# electron_v011.net
KiCad netlist of a schematic drawn in EAGLE
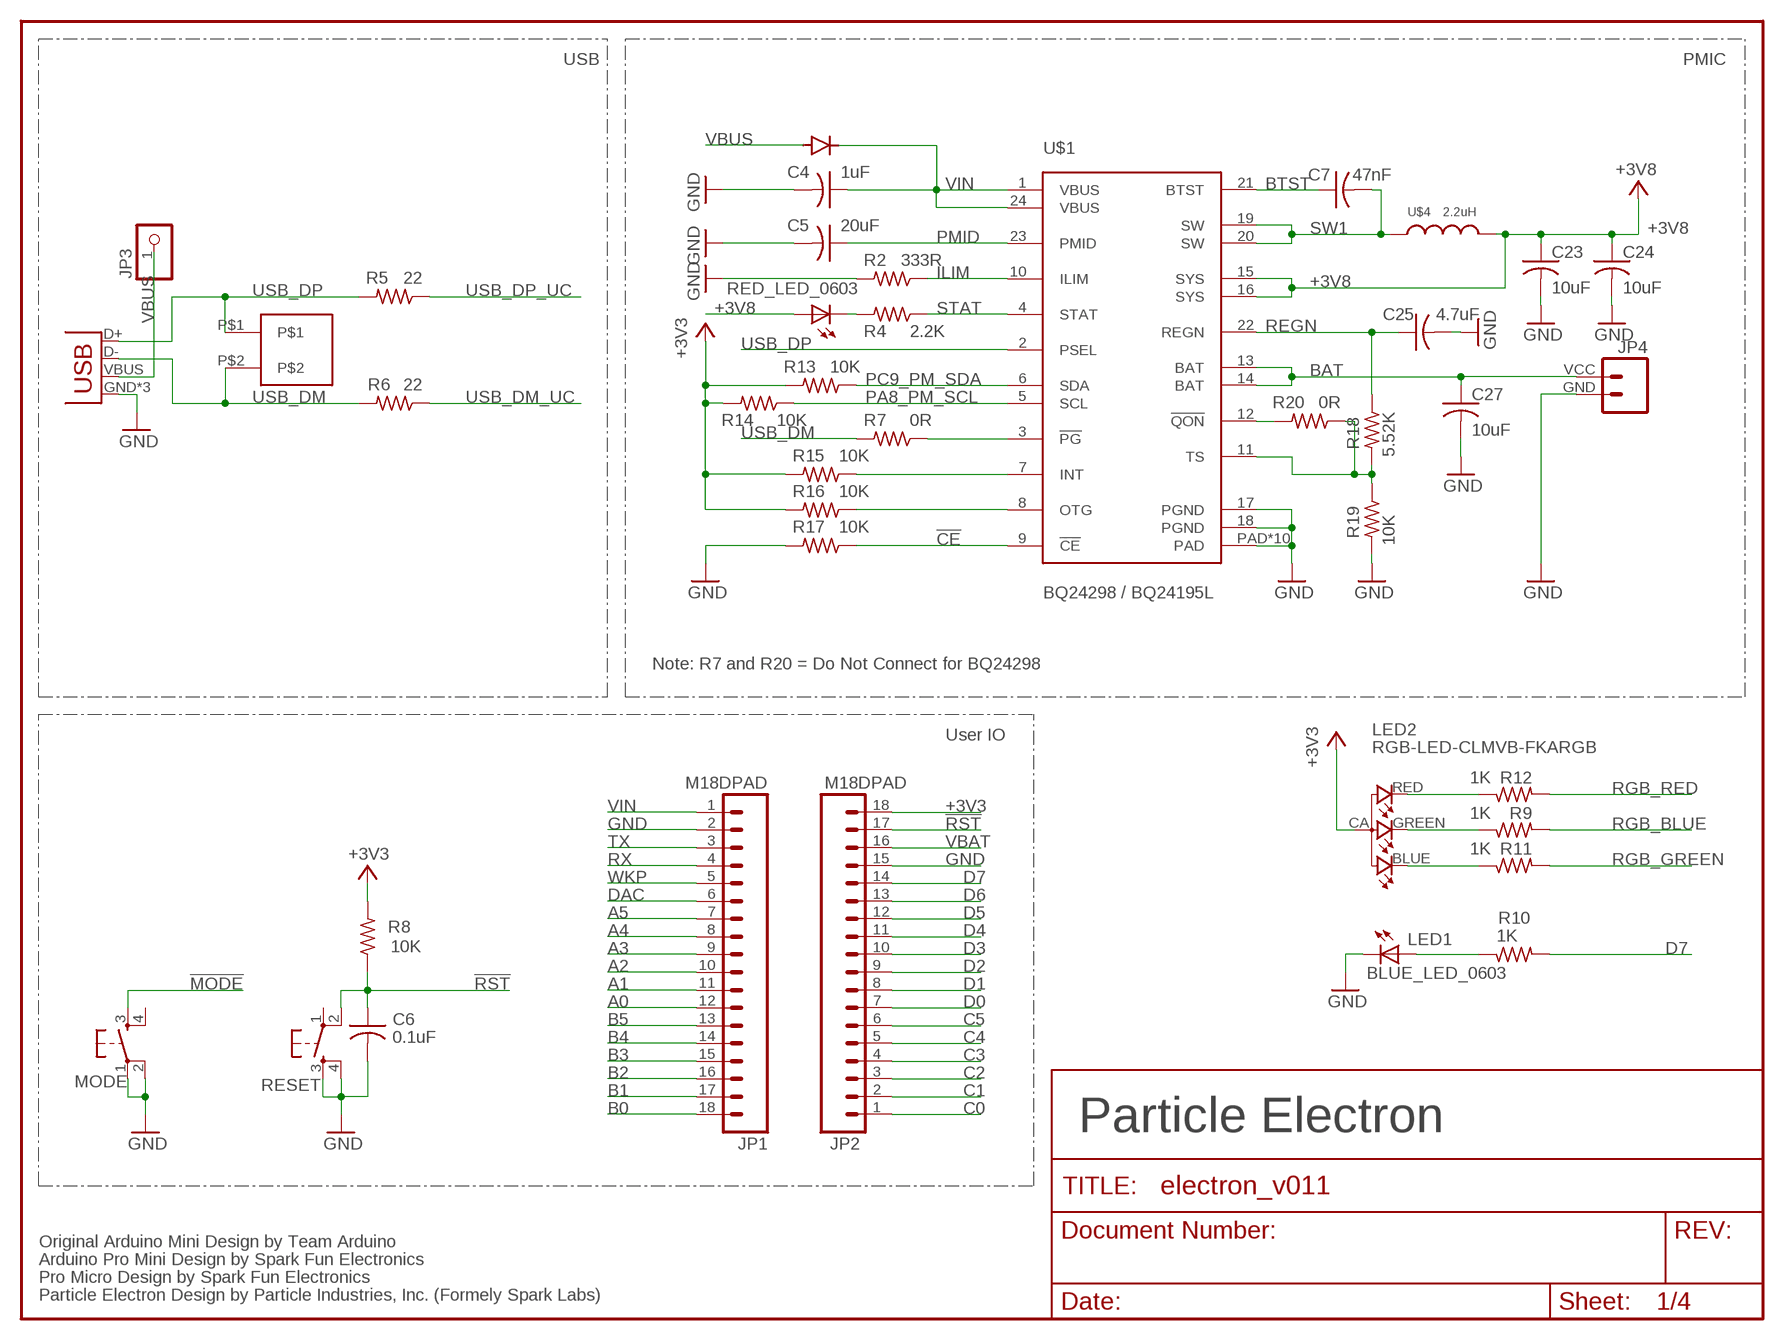
[diagram p0: schematic, sheet 1]
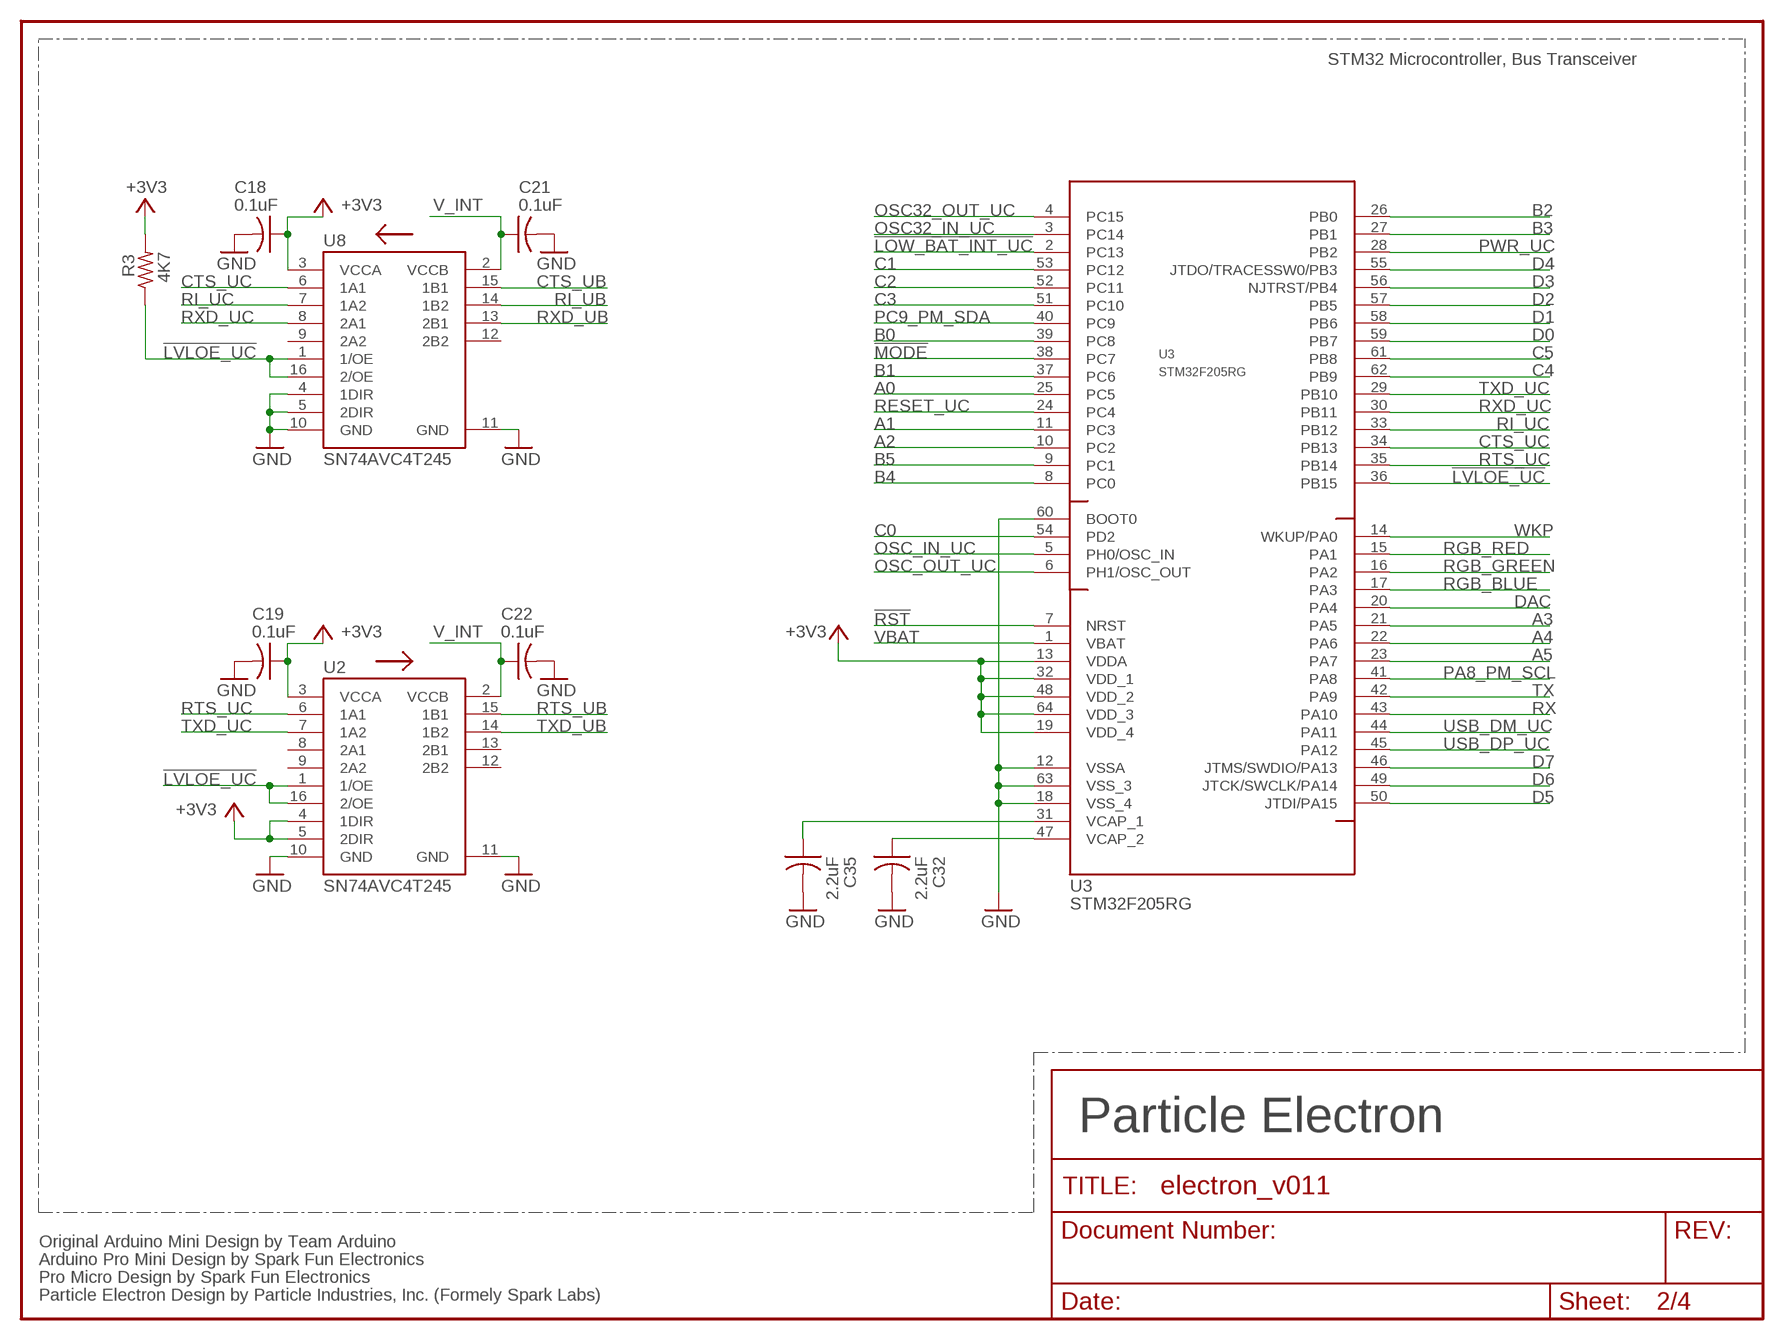
[diagram p1: schematic, sheet 2]
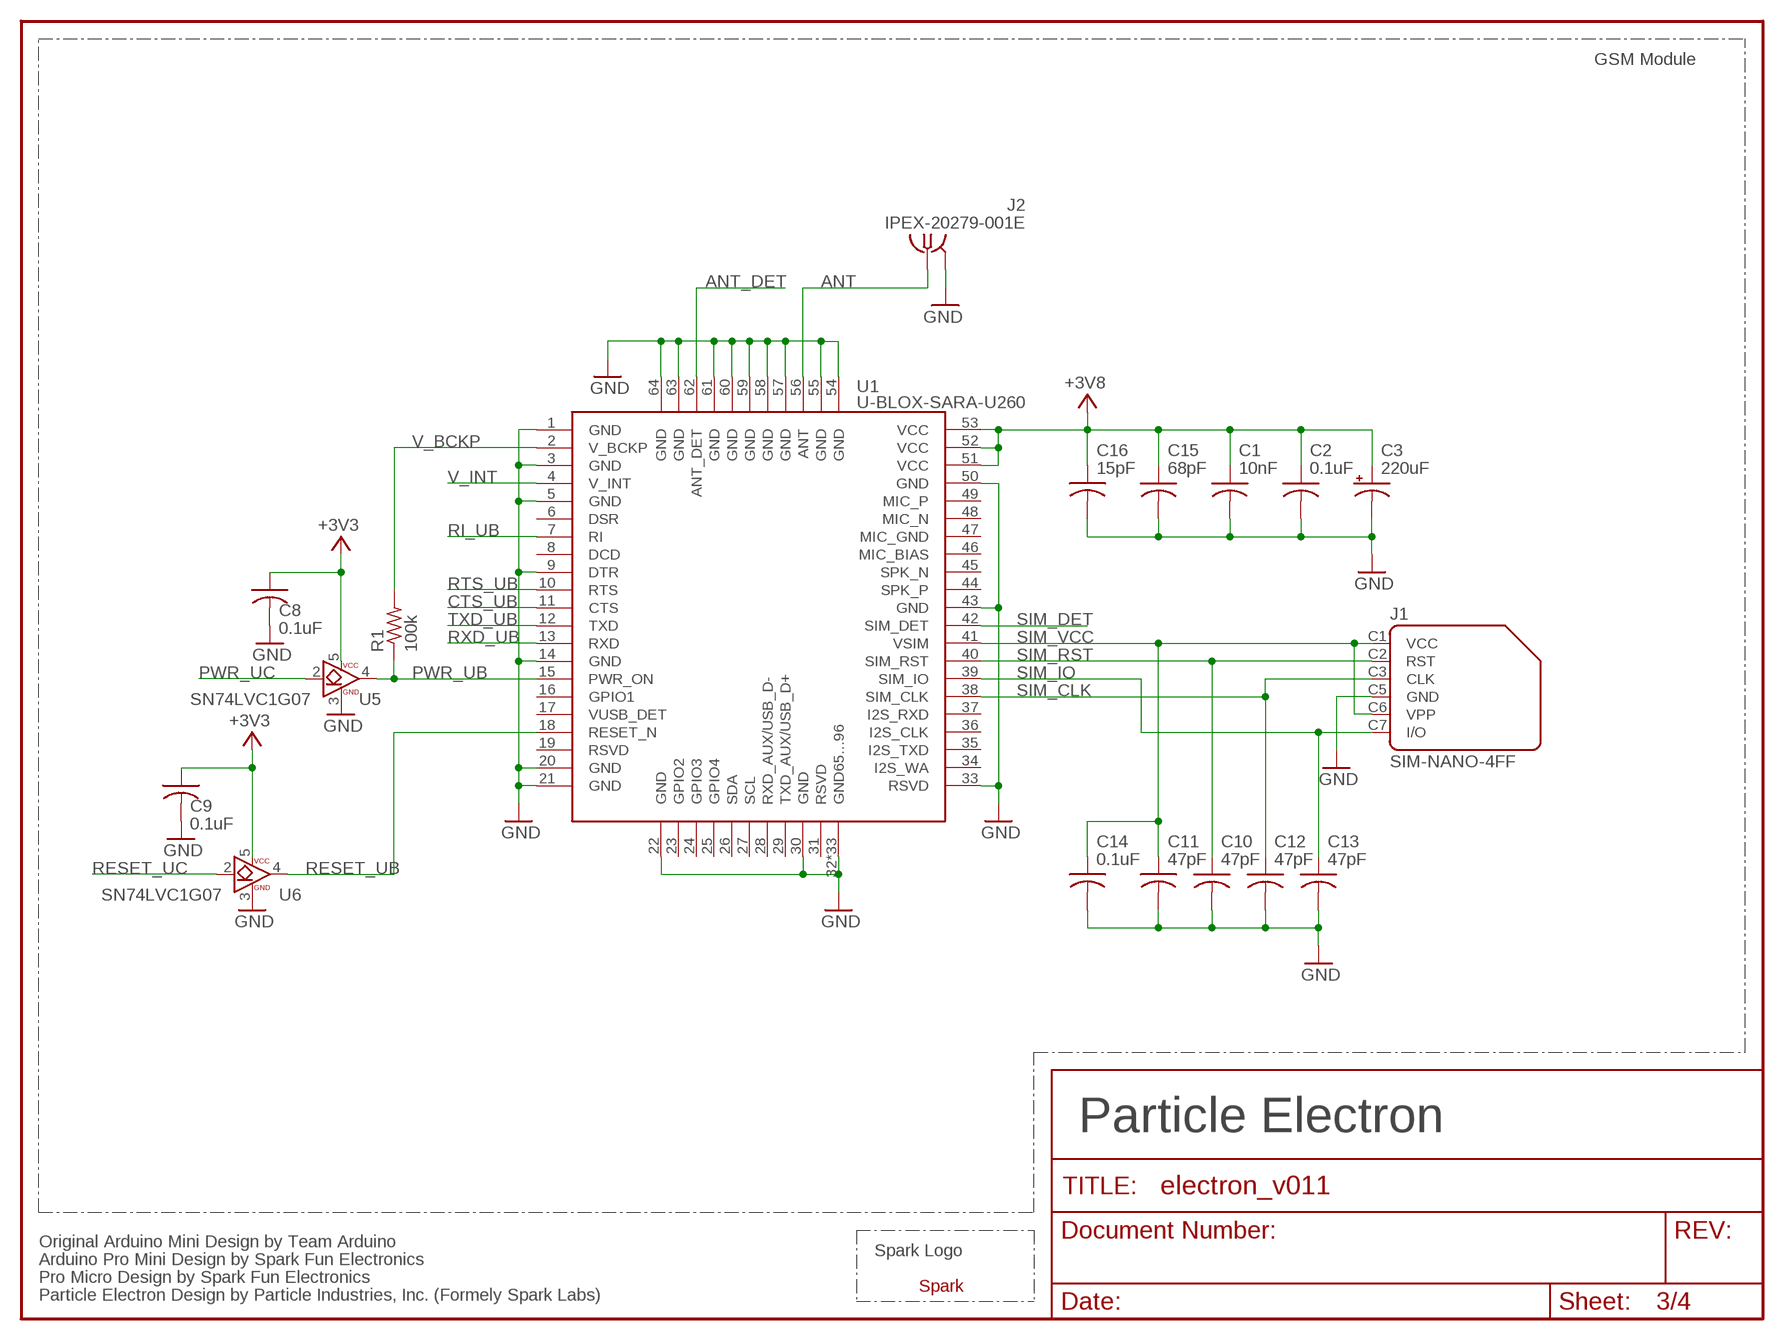
[diagram p2: schematic, sheet 3]
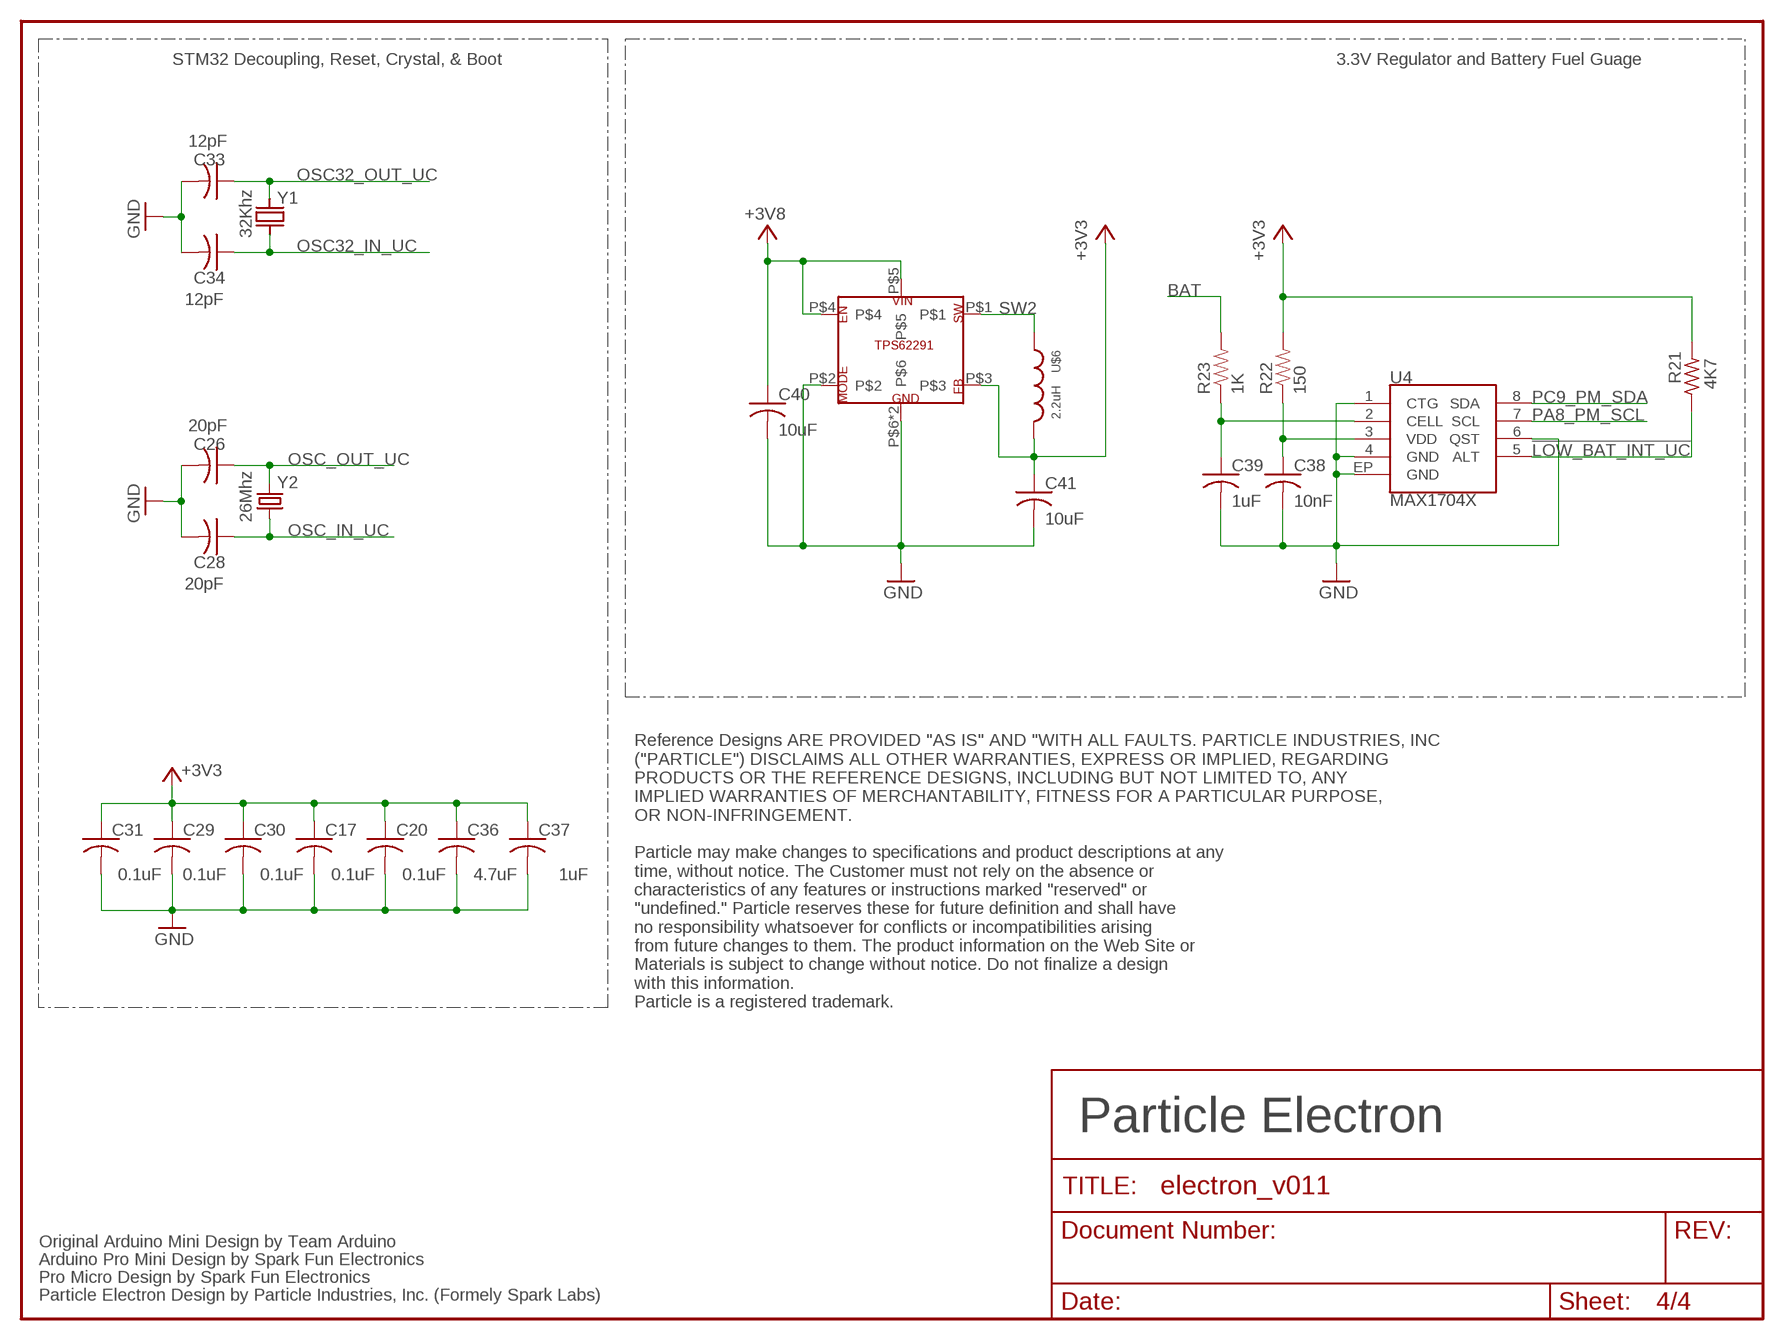
[diagram p3: schematic, sheet 4]

(export (version "E")
  (design (tool "Eeschema 10.0.6"))
  (components
    (comp (ref "C1")
      (value "10nF")
      (footprint "eagle-import:C0402_B")
      (libsource (lib "eagle-import") (part "C-US"))
    )
    (comp (ref "C2")
      (value "0.1uF")
      (footprint "eagle-import:C0402_B")
      (libsource (lib "eagle-import") (part "C-US"))
    )
    (comp (ref "C3")
      (value "220uF")
      (footprint "eagle-import:C_6032-28R")
      (libsource (lib "eagle-import") (part "CPOL-USC/6032-28R"))
    )
    (comp (ref "C8")
      (value "0.1uF")
      (footprint "eagle-import:C0402_B")
      (libsource (lib "eagle-import") (part "C-US"))
    )
    (comp (ref "C9")
      (value "0.1uF")
      (footprint "eagle-import:C0402_B")
      (libsource (lib "eagle-import") (part "C-US"))
    )
    (comp (ref "C10")
      (value "47pF")
      (footprint "eagle-import:C0402_B")
      (libsource (lib "eagle-import") (part "C-US"))
    )
    (comp (ref "C11")
      (value "47pF")
      (footprint "eagle-import:C0402_B")
      (libsource (lib "eagle-import") (part "C-US"))
    )
    (comp (ref "C12")
      (value "47pF")
      (footprint "eagle-import:C0402_B")
      (libsource (lib "eagle-import") (part "C-US"))
    )
    (comp (ref "C13")
      (value "47pF")
      (footprint "eagle-import:C0402_B")
      (libsource (lib "eagle-import") (part "C-US"))
    )
    (comp (ref "C14")
      (value "0.1uF")
      (footprint "eagle-import:C0402_B")
      (libsource (lib "eagle-import") (part "C-US"))
    )
    (comp (ref "C15")
      (value "68pF")
      (footprint "eagle-import:C0402_B")
      (libsource (lib "eagle-import") (part "C-US"))
    )
    (comp (ref "C16")
      (value "15pF")
      (footprint "eagle-import:C0402_B")
      (libsource (lib "eagle-import") (part "C-US"))
    )
    (comp (ref "J1")
      (value "SIM-NANO-4FF")
      (footprint "eagle-import:GCT-SIM8100")
      (libsource (lib "eagle-import") (part "SIM-NANO-4FF"))
    )
    (comp (ref "J2")
      (value "IPEX-20279-001E")
      (footprint "eagle-import:IPEX-20279-001E")
      (libsource (lib "eagle-import") (part "IPEX-20279-001E"))
    )
    (comp (ref "R1")
      (value "100k")
      (footprint "eagle-import:R0402_B")
      (libsource (lib "eagle-import") (part "R-US_"))
    )
    (comp (ref "U$2")
      (value "SPARK_LOGO2")
      (footprint "eagle-import:SPARK_LOGO2")
      (libsource (lib "eagle-import") (part "SPARK_LOGO2"))
    )
    (comp (ref "U1")
      (value "U-BLOX-SARA-U260")
      (footprint "eagle-import:U-BLOX-SARA-U2")
      (libsource (lib "eagle-import") (part "U-BLOX-SARA-U260"))
    )
    (comp (ref "U5")
      (value "SN74LVC1G07")
      (footprint "eagle-import:SC-70-5")
      (libsource (lib "eagle-import") (part "SN74LVC1G07"))
    )
    (comp (ref "U6")
      (value "SN74LVC1G07")
      (footprint "eagle-import:SC-70-5")
      (libsource (lib "eagle-import") (part "SN74LVC1G07"))
    )
    (comp (ref "BLUE_LED_0603")
      (value "LED0603")
      (footprint "eagle-import:LED-0603")
      (libsource (lib "eagle-import") (part "LED0603"))
    )
    (comp (ref "C4")
      (value "1uF")
      (footprint "eagle-import:C0603_B")
      (libsource (lib "eagle-import") (part "C-US0603"))
    )
    (comp (ref "C5")
      (value "20uF")
      (footprint "eagle-import:C0603_B")
      (libsource (lib "eagle-import") (part "C-US0603"))
    )
    (comp (ref "C6")
      (value "0.1uF")
      (footprint "eagle-import:C0402_B")
      (libsource (lib "eagle-import") (part "C-US"))
    )
    (comp (ref "C7")
      (value "47nF")
      (footprint "eagle-import:C0402_B")
      (libsource (lib "eagle-import") (part "C-US"))
    )
    (comp (ref "C23")
      (value "10uF")
      (footprint "eagle-import:C0603_B")
      (libsource (lib "eagle-import") (part "C-US0603"))
    )
    (comp (ref "C24")
      (value "10uF")
      (footprint "eagle-import:C0603_B")
      (libsource (lib "eagle-import") (part "C-US0603"))
    )
    (comp (ref "C25")
      (value "4.7uF")
      (footprint "eagle-import:C0603_B")
      (libsource (lib "eagle-import") (part "C-US0603"))
    )
    (comp (ref "C27")
      (value "10uF")
      (footprint "eagle-import:C0603_B")
      (libsource (lib "eagle-import") (part "C-US0603"))
    )
    (comp (ref "JP1")
      (value "M18DPAD")
      (footprint "eagle-import:1X18-D-PADS")
      (libsource (lib "eagle-import") (part "M18DPAD"))
    )
    (comp (ref "JP2")
      (value "M18DPAD")
      (footprint "eagle-import:1X18-D-PADS")
      (libsource (lib "eagle-import") (part "M18DPAD"))
    )
    (comp (ref "JP3")
      (value "PINHD-1X1")
      (footprint "eagle-import:1X01")
      (libsource (lib "eagle-import") (part "PINHD-1X1"))
    )
    (comp (ref "JP4")
      (value "M024UCON-15767")
      (footprint "eagle-import:JST-2-SMD-VERT")
      (libsource (lib "eagle-import") (part "M024UCON-15767"))
    )
    (comp (ref "LED2")
      (value "RGB-LED-CLMVB-FKARGB")
      (footprint "eagle-import:PLCC4-2MM-RGB")
      (libsource (lib "eagle-import") (part "RGB-LED-CLMVB-FKARGB"))
    )
    (comp (ref "MODE")
      (value "KMR211GLFS")
      (footprint "eagle-import:TACTILE_SWITCH_SMD")
      (libsource (lib "eagle-import") (part "TAC_SWITCHSMD"))
    )
    (comp (ref "R2")
      (value "333R")
      (footprint "eagle-import:R0402_B")
      (libsource (lib "eagle-import") (part "R-US_"))
    )
    (comp (ref "R4")
      (value "2.2K")
      (footprint "eagle-import:R0402_B")
      (libsource (lib "eagle-import") (part "R-US_"))
    )
    (comp (ref "R5")
      (value "22")
      (footprint "eagle-import:R0402_B")
      (libsource (lib "eagle-import") (part "R-US_"))
    )
    (comp (ref "R6")
      (value "22")
      (footprint "eagle-import:R0402_B")
      (libsource (lib "eagle-import") (part "R-US_"))
    )
    (comp (ref "R7")
      (value "0R")
      (footprint "eagle-import:R0402_B")
      (libsource (lib "eagle-import") (part "R-US_"))
    )
    (comp (ref "R8")
      (value "10K")
      (footprint "eagle-import:R0402_B")
      (libsource (lib "eagle-import") (part "R-US_"))
    )
    (comp (ref "R9")
      (value "1K")
      (footprint "eagle-import:R0402_B")
      (libsource (lib "eagle-import") (part "R-US_"))
    )
    (comp (ref "R10")
      (value "1K")
      (footprint "eagle-import:R0402_B")
      (libsource (lib "eagle-import") (part "R-US_"))
    )
    (comp (ref "R11")
      (value "1K")
      (footprint "eagle-import:R0402_B")
      (libsource (lib "eagle-import") (part "R-US_"))
    )
    (comp (ref "R12")
      (value "1K")
      (footprint "eagle-import:R0402_B")
      (libsource (lib "eagle-import") (part "R-US_"))
    )
    (comp (ref "R13")
      (value "10K")
      (footprint "eagle-import:R0402_B")
      (libsource (lib "eagle-import") (part "R-US_"))
    )
    (comp (ref "R14")
      (value "10K")
      (footprint "eagle-import:R0402_B")
      (libsource (lib "eagle-import") (part "R-US_"))
    )
    (comp (ref "R15")
      (value "10K")
      (footprint "eagle-import:R0402_B")
      (libsource (lib "eagle-import") (part "R-US_"))
    )
    (comp (ref "R16")
      (value "10K")
      (footprint "eagle-import:R0402_B")
      (libsource (lib "eagle-import") (part "R-US_"))
    )
    (comp (ref "R17")
      (value "10K")
      (footprint "eagle-import:R0402_B")
      (libsource (lib "eagle-import") (part "R-US_"))
    )
    (comp (ref "R18")
      (value "5.52K")
      (footprint "eagle-import:R0402_B")
      (libsource (lib "eagle-import") (part "R-US_"))
    )
    (comp (ref "R19")
      (value "10K")
      (footprint "eagle-import:R0402_B")
      (libsource (lib "eagle-import") (part "R-US_"))
    )
    (comp (ref "R20")
      (value "0R")
      (footprint "eagle-import:R0402_B")
      (libsource (lib "eagle-import") (part "R-US_"))
    )
    (comp (ref "RED_LED_0603")
      (value "LED0603")
      (footprint "eagle-import:LED-0603")
      (libsource (lib "eagle-import") (part "LED0603"))
    )
    (comp (ref "RESET")
      (value "KMR211GLFS")
      (footprint "eagle-import:TACTILE_SWITCH_SMD")
      (libsource (lib "eagle-import") (part "TAC_SWITCHSMD"))
    )
    (comp (ref "U$1")
      (value "BQ24298 / BQ24195L")
      (footprint "eagle-import:QFN24")
      (libsource (lib "eagle-import") (part "BQ24298RTWR"))
    )
    (comp (ref "U$3")
      (value "DIODE")
      (footprint "eagle-import:DIODE-DO-220AA(SMP)")
      (libsource (lib "eagle-import") (part "DIODE"))
    )
    (comp (ref "U$4")
      (value "2.2uH")
      (footprint "eagle-import:INDUCTOR-4020")
      (libsource (lib "eagle-import") (part "INDUCTORH"))
    )
    (comp (ref "U$7")
      (value "M02_0.05_HEADER")
      (footprint "eagle-import:M02_0.05_HEADER")
      (libsource (lib "eagle-import") (part "M02_0.05_HEADER"))
    )
    (comp (ref "X1")
      (value "USB-MICROB")
      (footprint "eagle-import:USB-MICROB-SLOT-HOLE")
      (libsource (lib "eagle-import") (part "USBUSB-MICROB-SLOT-HOLE"))
    )
    (comp (ref "C18")
      (value "0.1uF")
      (footprint "eagle-import:C0402_B")
      (libsource (lib "eagle-import") (part "C-US"))
    )
    (comp (ref "C19")
      (value "0.1uF")
      (footprint "eagle-import:C0402_B")
      (libsource (lib "eagle-import") (part "C-US"))
    )
    (comp (ref "C21")
      (value "0.1uF")
      (footprint "eagle-import:C0402_B")
      (libsource (lib "eagle-import") (part "C-US"))
    )
    (comp (ref "C22")
      (value "0.1uF")
      (footprint "eagle-import:C0402_B")
      (libsource (lib "eagle-import") (part "C-US"))
    )
    (comp (ref "C32")
      (value "2.2uF")
      (footprint "eagle-import:C0402_B")
      (libsource (lib "eagle-import") (part "C-US"))
    )
    (comp (ref "C35")
      (value "2.2uF")
      (footprint "eagle-import:C0402_B")
      (libsource (lib "eagle-import") (part "C-US"))
    )
    (comp (ref "R3")
      (value "4K7")
      (footprint "eagle-import:R0402_B")
      (libsource (lib "eagle-import") (part "R-US_"))
    )
    (comp (ref "U2")
      (value "SN74AVC4T245")
      (footprint "eagle-import:UFQFN-16")
      (libsource (lib "eagle-import") (part "SN74AVC4T245"))
    )
    (comp (ref "U3")
      (value "STM32F205RG")
      (footprint "eagle-import:LQFP64")
      (libsource (lib "eagle-import") (part "STM32F20XR"))
    )
    (comp (ref "U8")
      (value "SN74AVC4T245")
      (footprint "eagle-import:UFQFN-16")
      (libsource (lib "eagle-import") (part "SN74AVC4T245"))
    )
    (comp (ref "C17")
      (value "0.1uF")
      (footprint "eagle-import:C0402_B")
      (libsource (lib "eagle-import") (part "C-US"))
    )
    (comp (ref "C20")
      (value "0.1uF")
      (footprint "eagle-import:C0402_B")
      (libsource (lib "eagle-import") (part "C-US"))
    )
    (comp (ref "C26")
      (value "20pF")
      (footprint "eagle-import:C0402_B")
      (libsource (lib "eagle-import") (part "C-US"))
    )
    (comp (ref "C28")
      (value "20pF")
      (footprint "eagle-import:C0402_B")
      (libsource (lib "eagle-import") (part "C-US"))
    )
    (comp (ref "C29")
      (value "0.1uF")
      (footprint "eagle-import:C0402_B")
      (libsource (lib "eagle-import") (part "C-US"))
    )
    (comp (ref "C30")
      (value "0.1uF")
      (footprint "eagle-import:C0402_B")
      (libsource (lib "eagle-import") (part "C-US"))
    )
    (comp (ref "C31")
      (value "0.1uF")
      (footprint "eagle-import:C0402_B")
      (libsource (lib "eagle-import") (part "C-US"))
    )
    (comp (ref "C33")
      (value "12pF")
      (footprint "eagle-import:C0402_B")
      (libsource (lib "eagle-import") (part "C-US"))
    )
    (comp (ref "C34")
      (value "12pF")
      (footprint "eagle-import:C0402_B")
      (libsource (lib "eagle-import") (part "C-US"))
    )
    (comp (ref "C36")
      (value "4.7uF")
      (footprint "eagle-import:C0402_B")
      (libsource (lib "eagle-import") (part "C-US"))
    )
    (comp (ref "C37")
      (value "1uF")
      (footprint "eagle-import:C0402_B")
      (libsource (lib "eagle-import") (part "C-US"))
    )
    (comp (ref "C38")
      (value "10nF")
      (footprint "eagle-import:C0402_B")
      (libsource (lib "eagle-import") (part "C-US"))
    )
    (comp (ref "C39")
      (value "1uF")
      (footprint "eagle-import:C0402_B")
      (libsource (lib "eagle-import") (part "C-US"))
    )
    (comp (ref "C40")
      (value "10uF")
      (footprint "eagle-import:C0603_B")
      (libsource (lib "eagle-import") (part "C-US0603"))
    )
    (comp (ref "C41")
      (value "10uF")
      (footprint "eagle-import:C0603_B")
      (libsource (lib "eagle-import") (part "C-US0603"))
    )
    (comp (ref "R21")
      (value "4K7")
      (footprint "eagle-import:R0402_B")
      (libsource (lib "eagle-import") (part "R-US_"))
    )
    (comp (ref "R22")
      (value "150")
      (footprint "eagle-import:0603-RES")
      (libsource (lib "eagle-import") (part "RESISTOR0603-RES"))
    )
    (comp (ref "R23")
      (value "1K")
      (footprint "eagle-import:0603-RES")
      (libsource (lib "eagle-import") (part "RESISTOR0603-RES"))
    )
    (comp (ref "U$5")
      (value "TPS62291DRV")
      (footprint "eagle-import:S-PWSON-N6")
      (libsource (lib "eagle-import") (part "TPS62291DRV"))
    )
    (comp (ref "U$6")
      (value "2.2uH")
      (footprint "eagle-import:INDUCTOR-4020")
      (libsource (lib "eagle-import") (part "INDUCTORH"))
    )
    (comp (ref "U4")
      (value "MAX1704X")
      (footprint "eagle-import:TDFN-8")
      (libsource (lib "eagle-import") (part "MAX1704X"))
    )
    (comp (ref "Y1")
      (value "32Khz")
      (footprint "eagle-import:FC135")
      (libsource (lib "eagle-import") (part "Q_FC135"))
    )
    (comp (ref "Y2")
      (value "26Mhz")
      (footprint "eagle-import:CRYSTAL-SMD-5X3")
      (libsource (lib "eagle-import") (part "CRYSTAL5X3"))
    )
  )
  (nets
    (net (code "1") (name "+3V3") (class "Default")
      (node (ref "C17") (pin "1") (pinfunction "1_1") (pintype "passive"))
      (node (ref "C18") (pin "1") (pinfunction "1_1") (pintype "passive"))
      (node (ref "C19") (pin "1") (pinfunction "1_1") (pintype "passive"))
      (node (ref "C20") (pin "1") (pinfunction "1_1") (pintype "passive"))
      (node (ref "C29") (pin "1") (pinfunction "1_1") (pintype "passive"))
      (node (ref "C30") (pin "1") (pinfunction "1_1") (pintype "passive"))
      (node (ref "C31") (pin "1") (pinfunction "1_1") (pintype "passive"))
      (node (ref "C36") (pin "1") (pinfunction "1_1") (pintype "passive"))
      (node (ref "C37") (pin "1") (pinfunction "1_1") (pintype "passive"))
      (node (ref "C41") (pin "1") (pinfunction "1_1") (pintype "passive"))
      (node (ref "C8") (pin "1") (pinfunction "1_1") (pintype "passive"))
      (node (ref "C9") (pin "1") (pinfunction "1_1") (pintype "passive"))
      (node (ref "JP2") (pin "18") (pinfunction "18_18") (pintype "passive"))
      (node (ref "LED2") (pin "CA") (pinfunction "1_CA") (pintype "passive"))
      (node (ref "R13") (pin "2") (pinfunction "2_2") (pintype "passive"))
      (node (ref "R14") (pin "2") (pinfunction "2_2") (pintype "passive"))
      (node (ref "R15") (pin "2") (pinfunction "2_2") (pintype "passive"))
      (node (ref "R16") (pin "2") (pinfunction "2_2") (pintype "passive"))
      (node (ref "R21") (pin "2") (pinfunction "2_2") (pintype "passive"))
      (node (ref "R22") (pin "2") (pinfunction "2_2") (pintype "passive"))
      (node (ref "R3") (pin "2") (pinfunction "2_2") (pintype "passive"))
      (node (ref "R8") (pin "2") (pinfunction "2_2") (pintype "passive"))
      (node (ref "U$5") (pin "P$3") (pinfunction "P$3_P$3") (pintype "bidirectional"))
      (node (ref "U$6") (pin "P$2") (pinfunction "2_P$2") (pintype "passive"))
      (node (ref "U2") (pin "3") (pinfunction "VCCA_3") (pintype "bidirectional"))
      (node (ref "U2") (pin "4") (pinfunction "1DIR_4") (pintype "bidirectional"))
      (node (ref "U2") (pin "5") (pinfunction "2DIR_5") (pintype "bidirectional"))
      (node (ref "U3") (pin "13") (pinfunction "VDDA_13") (pintype "power_in"))
      (node (ref "U3") (pin "19") (pinfunction "VDD_4_19") (pintype "power_in"))
      (node (ref "U3") (pin "32") (pinfunction "VDD_1_32") (pintype "power_in"))
      (node (ref "U3") (pin "48") (pinfunction "VDD_2_48") (pintype "power_in"))
      (node (ref "U3") (pin "64") (pinfunction "VDD_3_64") (pintype "power_in"))
      (node (ref "U5") (pin "5") (pinfunction "VCC_5") (pintype "bidirectional"))
      (node (ref "U6") (pin "5") (pinfunction "VCC_5") (pintype "bidirectional"))
      (node (ref "U8") (pin "3") (pinfunction "VCCA_3") (pintype "bidirectional"))
    )
    (net (code "2") (name "+3V8") (class "Default")
      (node (ref "C1") (pin "1") (pinfunction "1_1") (pintype "passive"))
      (node (ref "C15") (pin "1") (pinfunction "1_1") (pintype "passive"))
      (node (ref "C16") (pin "1") (pinfunction "1_1") (pintype "passive"))
      (node (ref "C2") (pin "1") (pinfunction "1_1") (pintype "passive"))
      (node (ref "C23") (pin "1") (pinfunction "1_1") (pintype "passive"))
      (node (ref "C24") (pin "1") (pinfunction "1_1") (pintype "passive"))
      (node (ref "C3") (pin "+") (pinfunction "+_+") (pintype "passive"))
      (node (ref "C40") (pin "1") (pinfunction "1_1") (pintype "passive"))
      (node (ref "RED_LED_0603") (pin "A") (pinfunction "A_A") (pintype "passive"))
      (node (ref "U$1") (pin "15") (pinfunction "SYS_15") (pintype "power_in"))
      (node (ref "U$1") (pin "16") (pinfunction "SYS_16") (pintype "power_in"))
      (node (ref "U$4") (pin "P$2") (pinfunction "2_P$2") (pintype "passive"))
      (node (ref "U$5") (pin "P$4") (pinfunction "P$4_P$4") (pintype "bidirectional"))
      (node (ref "U$5") (pin "P$5") (pinfunction "P$5_P$5") (pintype "bidirectional"))
      (node (ref "U1") (pin "51") (pinfunction "VCC_51") (pintype "bidirectional"))
      (node (ref "U1") (pin "52") (pinfunction "VCC_52") (pintype "bidirectional"))
      (node (ref "U1") (pin "53") (pinfunction "VCC_53") (pintype "bidirectional"))
    )
    (net (code "3") (name "A0") (class "Default")
      (node (ref "JP1") (pin "12") (pinfunction "12_12") (pintype "passive"))
      (node (ref "U3") (pin "25") (pinfunction "PC5_25") (pintype "bidirectional"))
    )
    (net (code "4") (name "A1") (class "Default")
      (node (ref "JP1") (pin "11") (pinfunction "11_11") (pintype "passive"))
      (node (ref "U3") (pin "11") (pinfunction "PC3_11") (pintype "bidirectional"))
    )
    (net (code "5") (name "A2") (class "Default")
      (node (ref "JP1") (pin "10") (pinfunction "10_10") (pintype "passive"))
      (node (ref "U3") (pin "10") (pinfunction "PC2_10") (pintype "bidirectional"))
    )
    (net (code "6") (name "A3") (class "Default")
      (node (ref "JP1") (pin "9") (pinfunction "9_9") (pintype "passive"))
      (node (ref "U3") (pin "21") (pinfunction "PA5_21") (pintype "bidirectional"))
    )
    (net (code "7") (name "A4") (class "Default")
      (node (ref "JP1") (pin "8") (pinfunction "8_8") (pintype "passive"))
      (node (ref "U3") (pin "22") (pinfunction "PA6_22") (pintype "bidirectional"))
    )
    (net (code "8") (name "A5") (class "Default")
      (node (ref "JP1") (pin "7") (pinfunction "7_7") (pintype "passive"))
      (node (ref "U3") (pin "23") (pinfunction "PA7_23") (pintype "bidirectional"))
    )
    (net (code "9") (name "ANT") (class "Default")
      (node (ref "J2") (pin "1") (pinfunction "1_1") (pintype "passive"))
      (node (ref "U1") (pin "56") (pinfunction "ANT_56") (pintype "bidirectional"))
    )
    (net (code "10") (name "ANT_DET") (class "Default")
      (node (ref "U1") (pin "62") (pinfunction "ANT_DET_62") (pintype "bidirectional"))
    )
    (net (code "11") (name "B0") (class "Default")
      (node (ref "JP1") (pin "18") (pinfunction "18_18") (pintype "passive"))
      (node (ref "U3") (pin "39") (pinfunction "PC8_39") (pintype "bidirectional"))
    )
    (net (code "12") (name "B1") (class "Default")
      (node (ref "JP1") (pin "17") (pinfunction "17_17") (pintype "passive"))
      (node (ref "U3") (pin "37") (pinfunction "PC6_37") (pintype "bidirectional"))
    )
    (net (code "13") (name "B2") (class "Default")
      (node (ref "JP1") (pin "16") (pinfunction "16_16") (pintype "passive"))
      (node (ref "U3") (pin "26") (pinfunction "PB0_26") (pintype "bidirectional"))
    )
    (net (code "14") (name "B3") (class "Default")
      (node (ref "JP1") (pin "15") (pinfunction "15_15") (pintype "passive"))
      (node (ref "U3") (pin "27") (pinfunction "PB1_27") (pintype "bidirectional"))
    )
    (net (code "15") (name "B4") (class "Default")
      (node (ref "JP1") (pin "14") (pinfunction "14_14") (pintype "passive"))
      (node (ref "U3") (pin "8") (pinfunction "PC0_8") (pintype "bidirectional"))
    )
    (net (code "16") (name "B5") (class "Default")
      (node (ref "JP1") (pin "13") (pinfunction "13_13") (pintype "passive"))
      (node (ref "U3") (pin "9") (pinfunction "PC1_9") (pintype "bidirectional"))
    )
    (net (code "17") (name "BAT") (class "Default")
      (node (ref "C27") (pin "1") (pinfunction "1_1") (pintype "passive"))
      (node (ref "JP4") (pin "VCC") (pinfunction "2_VCC") (pintype "passive"))
      (node (ref "R23") (pin "2") (pinfunction "2_2") (pintype "passive"))
      (node (ref "U$1") (pin "13") (pinfunction "BAT_13") (pintype "passive"))
      (node (ref "U$1") (pin "14") (pinfunction "BAT_14") (pintype "power_in"))
    )
    (net (code "18") (name "BTST") (class "Default")
      (node (ref "C7") (pin "1") (pinfunction "1_1") (pintype "passive"))
      (node (ref "U$1") (pin "21") (pinfunction "BTST_21") (pintype "bidirectional"))
    )
    (net (code "19") (name "C0") (class "Default")
      (node (ref "JP2") (pin "1") (pinfunction "1_1") (pintype "passive"))
      (node (ref "U3") (pin "54") (pinfunction "PD2_54") (pintype "bidirectional"))
    )
    (net (code "20") (name "C1") (class "Default")
      (node (ref "JP2") (pin "2") (pinfunction "2_2") (pintype "passive"))
      (node (ref "U3") (pin "53") (pinfunction "PC12_53") (pintype "bidirectional"))
    )
    (net (code "21") (name "C2") (class "Default")
      (node (ref "JP2") (pin "3") (pinfunction "3_3") (pintype "passive"))
      (node (ref "U3") (pin "52") (pinfunction "PC11_52") (pintype "bidirectional"))
    )
    (net (code "22") (name "C3") (class "Default")
      (node (ref "JP2") (pin "4") (pinfunction "4_4") (pintype "passive"))
      (node (ref "U3") (pin "51") (pinfunction "PC10_51") (pintype "bidirectional"))
    )
    (net (code "23") (name "C4") (class "Default")
      (node (ref "JP2") (pin "5") (pinfunction "5_5") (pintype "passive"))
      (node (ref "U3") (pin "62") (pinfunction "PB9_62") (pintype "bidirectional"))
    )
    (net (code "24") (name "C5") (class "Default")
      (node (ref "JP2") (pin "6") (pinfunction "6_6") (pintype "passive"))
      (node (ref "U3") (pin "61") (pinfunction "PB8_61") (pintype "bidirectional"))
    )
    (net (code "25") (name "CTS_UB") (class "Default")
      (node (ref "U1") (pin "11") (pinfunction "CTS_11") (pintype "bidirectional"))
      (node (ref "U8") (pin "15") (pinfunction "1B1_15") (pintype "bidirectional"))
    )
    (net (code "26") (name "CTS_UC") (class "Default")
      (node (ref "U3") (pin "34") (pinfunction "PB13_34") (pintype "bidirectional"))
      (node (ref "U8") (pin "6") (pinfunction "1A1_6") (pintype "bidirectional"))
    )
    (net (code "27") (name "D0") (class "Default")
      (node (ref "JP2") (pin "7") (pinfunction "7_7") (pintype "passive"))
      (node (ref "U3") (pin "59") (pinfunction "PB7_59") (pintype "bidirectional"))
    )
    (net (code "28") (name "D1") (class "Default")
      (node (ref "JP2") (pin "8") (pinfunction "8_8") (pintype "passive"))
      (node (ref "U3") (pin "58") (pinfunction "PB6_58") (pintype "bidirectional"))
    )
    (net (code "29") (name "D2") (class "Default")
      (node (ref "JP2") (pin "9") (pinfunction "9_9") (pintype "passive"))
      (node (ref "U3") (pin "57") (pinfunction "PB5_57") (pintype "bidirectional"))
    )
    (net (code "30") (name "D3") (class "Default")
      (node (ref "JP2") (pin "10") (pinfunction "10_10") (pintype "passive"))
      (node (ref "U3") (pin "56") (pinfunction "NJTRST/PB4_56") (pintype "bidirectional"))
    )
    (net (code "31") (name "D4") (class "Default")
      (node (ref "JP2") (pin "11") (pinfunction "11_11") (pintype "passive"))
      (node (ref "U3") (pin "55") (pinfunction "JTDO/TRACESSW0/PB3_55") (pintype "bidirectional"))
    )
    (net (code "32") (name "D5") (class "Default")
      (node (ref "JP2") (pin "12") (pinfunction "12_12") (pintype "passive"))
      (node (ref "U3") (pin "50") (pinfunction "JTDI/PA15_50") (pintype "bidirectional"))
    )
    (net (code "33") (name "D6") (class "Default")
      (node (ref "JP2") (pin "13") (pinfunction "13_13") (pintype "passive"))
      (node (ref "U3") (pin "49") (pinfunction "JTCK/SWCLK/PA14_49") (pintype "bidirectional"))
    )
    (net (code "34") (name "D7") (class "Default")
      (node (ref "JP2") (pin "14") (pinfunction "14_14") (pintype "passive"))
      (node (ref "R10") (pin "2") (pinfunction "2_2") (pintype "passive"))
      (node (ref "U3") (pin "46") (pinfunction "JTMS/SWDIO/PA13_46") (pintype "bidirectional"))
    )
    (net (code "35") (name "DAC") (class "Default")
      (node (ref "JP1") (pin "6") (pinfunction "6_6") (pintype "passive"))
      (node (ref "U3") (pin "20") (pinfunction "PA4_20") (pintype "bidirectional"))
    )
    (net (code "36") (name "GND") (class "Default")
      (node (ref "BLUE_LED_0603") (pin "C") (pinfunction "C_C") (pintype "passive"))
      (node (ref "C1") (pin "2") (pinfunction "2_2") (pintype "passive"))
      (node (ref "C10") (pin "2") (pinfunction "2_2") (pintype "passive"))
      (node (ref "C11") (pin "2") (pinfunction "2_2") (pintype "passive"))
      (node (ref "C12") (pin "2") (pinfunction "2_2") (pintype "passive"))
      (node (ref "C13") (pin "2") (pinfunction "2_2") (pintype "passive"))
      (node (ref "C14") (pin "2") (pinfunction "2_2") (pintype "passive"))
      (node (ref "C15") (pin "2") (pinfunction "2_2") (pintype "passive"))
      (node (ref "C16") (pin "2") (pinfunction "2_2") (pintype "passive"))
      (node (ref "C17") (pin "2") (pinfunction "2_2") (pintype "passive"))
      (node (ref "C18") (pin "2") (pinfunction "2_2") (pintype "passive"))
      (node (ref "C19") (pin "2") (pinfunction "2_2") (pintype "passive"))
      (node (ref "C2") (pin "2") (pinfunction "2_2") (pintype "passive"))
      (node (ref "C20") (pin "2") (pinfunction "2_2") (pintype "passive"))
      (node (ref "C21") (pin "2") (pinfunction "2_2") (pintype "passive"))
      (node (ref "C22") (pin "2") (pinfunction "2_2") (pintype "passive"))
      (node (ref "C23") (pin "2") (pinfunction "2_2") (pintype "passive"))
      (node (ref "C24") (pin "2") (pinfunction "2_2") (pintype "passive"))
      (node (ref "C25") (pin "2") (pinfunction "2_2") (pintype "passive"))
      (node (ref "C26") (pin "2") (pinfunction "2_2") (pintype "passive"))
      (node (ref "C27") (pin "2") (pinfunction "2_2") (pintype "passive"))
      (node (ref "C28") (pin "2") (pinfunction "2_2") (pintype "passive"))
      (node (ref "C29") (pin "2") (pinfunction "2_2") (pintype "passive"))
      (node (ref "C3") (pin "-") (pinfunction "-_-") (pintype "passive"))
      (node (ref "C30") (pin "2") (pinfunction "2_2") (pintype "passive"))
      (node (ref "C31") (pin "2") (pinfunction "2_2") (pintype "passive"))
      (node (ref "C32") (pin "2") (pinfunction "2_2") (pintype "passive"))
      (node (ref "C33") (pin "2") (pinfunction "2_2") (pintype "passive"))
      (node (ref "C34") (pin "2") (pinfunction "2_2") (pintype "passive"))
      (node (ref "C35") (pin "2") (pinfunction "2_2") (pintype "passive"))
      (node (ref "C36") (pin "2") (pinfunction "2_2") (pintype "passive"))
      (node (ref "C37") (pin "2") (pinfunction "2_2") (pintype "passive"))
      (node (ref "C38") (pin "2") (pinfunction "2_2") (pintype "passive"))
      (node (ref "C39") (pin "2") (pinfunction "2_2") (pintype "passive"))
      (node (ref "C4") (pin "2") (pinfunction "2_2") (pintype "passive"))
      (node (ref "C40") (pin "2") (pinfunction "2_2") (pintype "passive"))
      (node (ref "C41") (pin "2") (pinfunction "2_2") (pintype "passive"))
      (node (ref "C5") (pin "2") (pinfunction "2_2") (pintype "passive"))
      (node (ref "C6") (pin "2") (pinfunction "2_2") (pintype "passive"))
      (node (ref "C8") (pin "2") (pinfunction "2_2") (pintype "passive"))
      (node (ref "C9") (pin "2") (pinfunction "2_2") (pintype "passive"))
      (node (ref "J1") (pin "C5") (pinfunction "GND_C5") (pintype "passive"))
      (node (ref "J2") (pin "2@1") (pinfunction "GND_2@1") (pintype "passive"))
      (node (ref "J2") (pin "2@2") (pinfunction "GND_2@2") (pintype "passive"))
      (node (ref "JP1") (pin "2") (pinfunction "2_2") (pintype "passive"))
      (node (ref "JP2") (pin "15") (pinfunction "15_15") (pintype "passive"))
      (node (ref "JP4") (pin "GND") (pinfunction "1_GND") (pintype "passive"))
      (node (ref "MODE") (pin "1") (pinfunction "1_1") (pintype "passive"))
      (node (ref "MODE") (pin "2") (pinfunction "2_2") (pintype "passive"))
      (node (ref "R17") (pin "2") (pinfunction "2_2") (pintype "passive"))
      (node (ref "R19") (pin "2") (pinfunction "2_2") (pintype "passive"))
      (node (ref "R2") (pin "2") (pinfunction "2_2") (pintype "passive"))
      (node (ref "RESET") (pin "3") (pinfunction "3_3") (pintype "passive"))
      (node (ref "RESET") (pin "4") (pinfunction "4_4") (pintype "passive"))
      (node (ref "U$1") (pin "17") (pinfunction "PGND_17") (pintype "passive"))
      (node (ref "U$1") (pin "18") (pinfunction "PGND_18") (pintype "passive"))
      (node (ref "U$1") (pin "PAD") (pinfunction "PAD_PAD") (pintype "power_in"))
      (node (ref "U$1") (pin "PAD@1") (pinfunction "PAD_PAD@1") (pintype "power_in"))
      (node (ref "U$1") (pin "PAD@2") (pinfunction "PAD_PAD@2") (pintype "power_in"))
      (node (ref "U$1") (pin "PAD@3") (pinfunction "PAD_PAD@3") (pintype "power_in"))
      (node (ref "U$1") (pin "PAD@4") (pinfunction "PAD_PAD@4") (pintype "power_in"))
      (node (ref "U$1") (pin "PAD@5") (pinfunction "PAD_PAD@5") (pintype "power_in"))
      (node (ref "U$1") (pin "PAD@6") (pinfunction "PAD_PAD@6") (pintype "power_in"))
      (node (ref "U$1") (pin "PAD@7") (pinfunction "PAD_PAD@7") (pintype "power_in"))
      (node (ref "U$1") (pin "PAD@8") (pinfunction "PAD_PAD@8") (pintype "power_in"))
      (node (ref "U$1") (pin "PAD@9") (pinfunction "PAD_PAD@9") (pintype "power_in"))
      (node (ref "U$5") (pin "P$2") (pinfunction "P$2_P$2") (pintype "bidirectional"))
      (node (ref "U$5") (pin "P$6") (pinfunction "P$6_P$6") (pintype "bidirectional"))
      (node (ref "U$5") (pin "TP") (pinfunction "P$6_TP") (pintype "bidirectional"))
      (node (ref "U1") (pin "1") (pinfunction "GND_1") (pintype "bidirectional"))
      (node (ref "U1") (pin "14") (pinfunction "GND_14") (pintype "bidirectional"))
      (node (ref "U1") (pin "20") (pinfunction "GND_20") (pintype "bidirectional"))
      (node (ref "U1") (pin "21") (pinfunction "GND_21") (pintype "bidirectional"))
      (node (ref "U1") (pin "22") (pinfunction "GND_22") (pintype "bidirectional"))
      (node (ref "U1") (pin "3") (pinfunction "GND_3") (pintype "bidirectional"))
      (node (ref "U1") (pin "30") (pinfunction "GND_30") (pintype "bidirectional"))
      (node (ref "U1") (pin "32") (pinfunction "GND65...96_32") (pintype "bidirectional"))
      (node (ref "U1") (pin "33") (pinfunction "RSVD_33") (pintype "bidirectional"))
      (node (ref "U1") (pin "43") (pinfunction "GND_43") (pintype "bidirectional"))
      (node (ref "U1") (pin "5") (pinfunction "GND_5") (pintype "bidirectional"))
      (node (ref "U1") (pin "50") (pinfunction "GND_50") (pintype "bidirectional"))
      (node (ref "U1") (pin "54") (pinfunction "GND_54") (pintype "bidirectional"))
      (node (ref "U1") (pin "55") (pinfunction "GND_55") (pintype "bidirectional"))
      (node (ref "U1") (pin "57") (pinfunction "GND_57") (pintype "bidirectional"))
      (node (ref "U1") (pin "58") (pinfunction "GND_58") (pintype "bidirectional"))
      (node (ref "U1") (pin "59") (pinfunction "GND_59") (pintype "bidirectional"))
      (node (ref "U1") (pin "60") (pinfunction "GND_60") (pintype "bidirectional"))
      (node (ref "U1") (pin "61") (pinfunction "GND_61") (pintype "bidirectional"))
      (node (ref "U1") (pin "63") (pinfunction "GND_63") (pintype "bidirectional"))
      (node (ref "U1") (pin "64") (pinfunction "GND_64") (pintype "bidirectional"))
      (node (ref "U1") (pin "65") (pinfunction "GND65...96_65") (pintype "bidirectional"))
      (node (ref "U1") (pin "66") (pinfunction "GND65...96_66") (pintype "bidirectional"))
      (node (ref "U1") (pin "67") (pinfunction "GND65...96_67") (pintype "bidirectional"))
      (node (ref "U1") (pin "68") (pinfunction "GND65...96_68") (pintype "bidirectional"))
      (node (ref "U1") (pin "69") (pinfunction "GND65...96_69") (pintype "bidirectional"))
      (node (ref "U1") (pin "70") (pinfunction "GND65...96_70") (pintype "bidirectional"))
      (node (ref "U1") (pin "71") (pinfunction "GND65...96_71") (pintype "bidirectional"))
      (node (ref "U1") (pin "72") (pinfunction "GND65...96_72") (pintype "bidirectional"))
      (node (ref "U1") (pin "73") (pinfunction "GND65...96_73") (pintype "bidirectional"))
      (node (ref "U1") (pin "74") (pinfunction "GND65...96_74") (pintype "bidirectional"))
      (node (ref "U1") (pin "75") (pinfunction "GND65...96_75") (pintype "bidirectional"))
      (node (ref "U1") (pin "76") (pinfunction "GND65...96_76") (pintype "bidirectional"))
      (node (ref "U1") (pin "77") (pinfunction "GND65...96_77") (pintype "bidirectional"))
      (node (ref "U1") (pin "78") (pinfunction "GND65...96_78") (pintype "bidirectional"))
      (node (ref "U1") (pin "79") (pinfunction "GND65...96_79") (pintype "bidirectional"))
      (node (ref "U1") (pin "80") (pinfunction "GND65...96_80") (pintype "bidirectional"))
      (node (ref "U1") (pin "81") (pinfunction "GND65...96_81") (pintype "bidirectional"))
      (node (ref "U1") (pin "82") (pinfunction "GND65...96_82") (pintype "bidirectional"))
      (node (ref "U1") (pin "83") (pinfunction "GND65...96_83") (pintype "bidirectional"))
      (node (ref "U1") (pin "84") (pinfunction "GND65...96_84") (pintype "bidirectional"))
      (node (ref "U1") (pin "85") (pinfunction "GND65...96_85") (pintype "bidirectional"))
      (node (ref "U1") (pin "86") (pinfunction "GND65...96_86") (pintype "bidirectional"))
      (node (ref "U1") (pin "87") (pinfunction "GND65...96_87") (pintype "bidirectional"))
      (node (ref "U1") (pin "88") (pinfunction "GND65...96_88") (pintype "bidirectional"))
      (node (ref "U1") (pin "89") (pinfunction "GND65...96_89") (pintype "bidirectional"))
      (node (ref "U1") (pin "9") (pinfunction "DTR_9") (pintype "bidirectional"))
      (node (ref "U1") (pin "90") (pinfunction "GND65...96_90") (pintype "bidirectional"))
      (node (ref "U1") (pin "91") (pinfunction "GND65...96_91") (pintype "bidirectional"))
      (node (ref "U1") (pin "92") (pinfunction "GND65...96_92") (pintype "bidirectional"))
      (node (ref "U1") (pin "93") (pinfunction "GND65...96_93") (pintype "bidirectional"))
      (node (ref "U1") (pin "94") (pinfunction "GND65...96_94") (pintype "bidirectional"))
      (node (ref "U1") (pin "95") (pinfunction "GND65...96_95") (pintype "bidirectional"))
      (node (ref "U1") (pin "96") (pinfunction "GND65...96_96") (pintype "bidirectional"))
      (node (ref "U2") (pin "10") (pinfunction "GND_10") (pintype "bidirectional"))
      (node (ref "U2") (pin "11") (pinfunction "GND_11") (pintype "bidirectional"))
      (node (ref "U3") (pin "12") (pinfunction "VSSA_12") (pintype "power_in"))
      (node (ref "U3") (pin "18") (pinfunction "VSS_4_18") (pintype "power_in"))
      (node (ref "U3") (pin "60") (pinfunction "BOOT0_60") (pintype "bidirectional"))
      (node (ref "U3") (pin "63") (pinfunction "VSS_3_63") (pintype "power_in"))
      (node (ref "U4") (pin "1") (pinfunction "CTG_1") (pintype "bidirectional"))
      (node (ref "U4") (pin "4") (pinfunction "GND_4") (pintype "bidirectional"))
      (node (ref "U4") (pin "6") (pinfunction "QST_6") (pintype "bidirectional"))
      (node (ref "U4") (pin "EP") (pinfunction "GND_EP") (pintype "bidirectional"))
      (node (ref "U5") (pin "3") (pinfunction "GND_3") (pintype "bidirectional"))
      (node (ref "U6") (pin "3") (pinfunction "GND_3") (pintype "bidirectional"))
      (node (ref "U8") (pin "10") (pinfunction "GND_10") (pintype "bidirectional"))
      (node (ref "U8") (pin "11") (pinfunction "GND_11") (pintype "bidirectional"))
      (node (ref "U8") (pin "4") (pinfunction "1DIR_4") (pintype "bidirectional"))
      (node (ref "U8") (pin "5") (pinfunction "2DIR_5") (pintype "bidirectional"))
      (node (ref "X1") (pin "GND") (pinfunction "GND_GND") (pintype "bidirectional"))
      (node (ref "X1") (pin "MT1") (pinfunction "GND_MT1") (pintype "bidirectional"))
      (node (ref "X1") (pin "MT2") (pinfunction "GND_MT2") (pintype "bidirectional"))
    )
    (net (code "37") (name "ILIM") (class "Default")
      (node (ref "R2") (pin "1") (pinfunction "1_1") (pintype "passive"))
      (node (ref "U$1") (pin "10") (pinfunction "ILIM_10") (pintype "output"))
    )
    (net (code "38") (name "LED1") (class "Default")
      (node (ref "BLUE_LED_0603") (pin "A") (pinfunction "A_A") (pintype "passive"))
      (node (ref "R10") (pin "1") (pinfunction "1_1") (pintype "passive"))
    )
    (net (code "39") (name "Net-(LED2-2)") (class "Default")
      (node (ref "LED2") (pin "BLUE") (pinfunction "2_BLUE") (pintype "passive"))
      (node (ref "R11") (pin "1") (pinfunction "1_1") (pintype "passive"))
    )
    (net (code "40") (name "Net-(LED2-3)") (class "Default")
      (node (ref "LED2") (pin "GREEN") (pinfunction "3_GREEN") (pintype "passive"))
      (node (ref "R9") (pin "1") (pinfunction "1_1") (pintype "passive"))
    )
    (net (code "41") (name "Net-(LED2-4)") (class "Default")
      (node (ref "LED2") (pin "RED") (pinfunction "4_RED") (pintype "passive"))
      (node (ref "R12") (pin "1") (pinfunction "1_1") (pintype "passive"))
    )
    (net (code "42") (name "Net-(R4-Pad2)") (class "Default")
      (node (ref "R4") (pin "2") (pinfunction "2_2") (pintype "passive"))
      (node (ref "RED_LED_0603") (pin "C") (pinfunction "C_C") (pintype "passive"))
    )
    (net (code "43") (name "Net-(U$1-INT)") (class "Default")
      (node (ref "R15") (pin "1") (pinfunction "1_1") (pintype "passive"))
      (node (ref "U$1") (pin "7") (pinfunction "INT_7") (pintype "bidirectional"))
    )
    (net (code "44") (name "Net-(U$1-OTG)") (class "Default")
      (node (ref "R16") (pin "1") (pinfunction "1_1") (pintype "passive"))
      (node (ref "U$1") (pin "8") (pinfunction "OTG_8") (pintype "bidirectional"))
    )
    (net (code "45") (name "Net-(U$1-TS)") (class "Default")
      (node (ref "R18") (pin "2") (pinfunction "2_2") (pintype "passive"))
      (node (ref "R19") (pin "1") (pinfunction "1_1") (pintype "passive"))
      (node (ref "R20") (pin "1") (pinfunction "1_1") (pintype "passive"))
      (node (ref "U$1") (pin "11") (pinfunction "TS_11") (pintype "bidirectional"))
    )
    (net (code "46") (name "Net-(U$1-~{PG})") (class "Default")
      (node (ref "R7") (pin "1") (pinfunction "1_1") (pintype "passive"))
      (node (ref "U$1") (pin "3") (pinfunction "~{PG}_3") (pintype "output"))
    )
    (net (code "47") (name "Net-(U$1-~{QON})") (class "Default")
      (node (ref "R20") (pin "2") (pinfunction "2_2") (pintype "passive"))
      (node (ref "U$1") (pin "12") (pinfunction "~{QON}_12") (pintype "bidirectional"))
    )
    (net (code "48") (name "Net-(U3-VCAP_1)") (class "Default")
      (node (ref "C35") (pin "1") (pinfunction "1_1") (pintype "passive"))
      (node (ref "U3") (pin "31") (pinfunction "VCAP_1_31") (pintype "power_in"))
    )
    (net (code "49") (name "Net-(U3-VCAP_2)") (class "Default")
      (node (ref "C32") (pin "1") (pinfunction "1_1") (pintype "passive"))
      (node (ref "U3") (pin "47") (pinfunction "VCAP_2_47") (pintype "power_in"))
    )
    (net (code "50") (name "Net-(U4-CELL)") (class "Default")
      (node (ref "C39") (pin "1") (pinfunction "1_1") (pintype "passive"))
      (node (ref "R23") (pin "1") (pinfunction "1_1") (pintype "passive"))
      (node (ref "U4") (pin "2") (pinfunction "CELL_2") (pintype "bidirectional"))
    )
    (net (code "51") (name "Net-(U4-VDD)") (class "Default")
      (node (ref "C38") (pin "1") (pinfunction "1_1") (pintype "passive"))
      (node (ref "R22") (pin "1") (pinfunction "1_1") (pintype "passive"))
      (node (ref "U4") (pin "3") (pinfunction "VDD_3") (pintype "bidirectional"))
    )
    (net (code "52") (name "OSC32_IN_UC") (class "Default")
      (node (ref "C34") (pin "1") (pinfunction "1_1") (pintype "passive"))
      (node (ref "U3") (pin "3") (pinfunction "PC14_3") (pintype "bidirectional"))
      (node (ref "Y1") (pin "X1") (pinfunction "1_X1") (pintype "passive"))
    )
    (net (code "53") (name "OSC32_OUT_UC") (class "Default")
      (node (ref "C33") (pin "1") (pinfunction "1_1") (pintype "passive"))
      (node (ref "U3") (pin "4") (pinfunction "PC15_4") (pintype "bidirectional"))
      (node (ref "Y1") (pin "X2") (pinfunction "2_X2") (pintype "passive"))
    )
    (net (code "54") (name "OSC_IN_UC") (class "Default")
      (node (ref "C28") (pin "1") (pinfunction "1_1") (pintype "passive"))
      (node (ref "U3") (pin "5") (pinfunction "PH0/OSC_IN_5") (pintype "bidirectional"))
      (node (ref "Y2") (pin "1") (pinfunction "1_1") (pintype "passive"))
    )
    (net (code "55") (name "OSC_OUT_UC") (class "Default")
      (node (ref "C26") (pin "1") (pinfunction "1_1") (pintype "passive"))
      (node (ref "U3") (pin "6") (pinfunction "PH1/OSC_OUT_6") (pintype "bidirectional"))
      (node (ref "Y2") (pin "3") (pinfunction "2_3") (pintype "passive"))
    )
    (net (code "56") (name "PA8_PM_SCL") (class "Default")
      (node (ref "R14") (pin "1") (pinfunction "1_1") (pintype "passive"))
      (node (ref "U$1") (pin "5") (pinfunction "SCL_5") (pintype "output"))
      (node (ref "U3") (pin "41") (pinfunction "PA8_41") (pintype "bidirectional"))
      (node (ref "U4") (pin "7") (pinfunction "SCL_7") (pintype "bidirectional"))
    )
    (net (code "57") (name "PC9_PM_SDA") (class "Default")
      (node (ref "R13") (pin "1") (pinfunction "1_1") (pintype "passive"))
      (node (ref "U$1") (pin "6") (pinfunction "SDA_6") (pintype "bidirectional"))
      (node (ref "U3") (pin "40") (pinfunction "PC9_40") (pintype "bidirectional"))
      (node (ref "U4") (pin "8") (pinfunction "SDA_8") (pintype "bidirectional"))
    )
    (net (code "58") (name "PMID") (class "Default")
      (node (ref "C5") (pin "1") (pinfunction "1_1") (pintype "passive"))
      (node (ref "U$1") (pin "23") (pinfunction "PMID_23") (pintype "passive"))
    )
    (net (code "59") (name "PWR_UB") (class "Default")
      (node (ref "R1") (pin "1") (pinfunction "1_1") (pintype "passive"))
      (node (ref "U1") (pin "15") (pinfunction "PWR_ON_15") (pintype "bidirectional"))
      (node (ref "U5") (pin "4") (pinfunction "B_4") (pintype "bidirectional"))
    )
    (net (code "60") (name "PWR_UC") (class "Default")
      (node (ref "U3") (pin "28") (pinfunction "PB2_28") (pintype "bidirectional"))
      (node (ref "U5") (pin "2") (pinfunction "A_2") (pintype "bidirectional"))
    )
    (net (code "61") (name "REGN") (class "Default")
      (node (ref "C25") (pin "1") (pinfunction "1_1") (pintype "passive"))
      (node (ref "R18") (pin "1") (pinfunction "1_1") (pintype "passive"))
      (node (ref "U$1") (pin "22") (pinfunction "REGN_22") (pintype "bidirectional"))
    )
    (net (code "62") (name "RESET_UB") (class "Default")
      (node (ref "U1") (pin "18") (pinfunction "RESET_N_18") (pintype "bidirectional"))
      (node (ref "U6") (pin "4") (pinfunction "B_4") (pintype "bidirectional"))
    )
    (net (code "63") (name "RESET_UC") (class "Default")
      (node (ref "U3") (pin "24") (pinfunction "PC4_24") (pintype "bidirectional"))
      (node (ref "U6") (pin "2") (pinfunction "A_2") (pintype "bidirectional"))
    )
    (net (code "64") (name "RGB_BLUE") (class "Default")
      (node (ref "R11") (pin "2") (pinfunction "2_2") (pintype "passive"))
      (node (ref "U3") (pin "17") (pinfunction "PA3_17") (pintype "bidirectional"))
    )
    (net (code "65") (name "RGB_GREEN") (class "Default")
      (node (ref "R9") (pin "2") (pinfunction "2_2") (pintype "passive"))
      (node (ref "U3") (pin "16") (pinfunction "PA2_16") (pintype "bidirectional"))
    )
    (net (code "66") (name "RGB_RED") (class "Default")
      (node (ref "R12") (pin "2") (pinfunction "2_2") (pintype "passive"))
      (node (ref "U3") (pin "15") (pinfunction "PA1_15") (pintype "bidirectional"))
    )
    (net (code "67") (name "RI_UB") (class "Default")
      (node (ref "U1") (pin "7") (pinfunction "RI_7") (pintype "bidirectional"))
      (node (ref "U8") (pin "14") (pinfunction "1B2_14") (pintype "bidirectional"))
    )
    (net (code "68") (name "RI_UC") (class "Default")
      (node (ref "U3") (pin "33") (pinfunction "PB12_33") (pintype "bidirectional"))
      (node (ref "U8") (pin "7") (pinfunction "1A2_7") (pintype "bidirectional"))
    )
    (net (code "69") (name "RTS_UB") (class "Default")
      (node (ref "U1") (pin "10") (pinfunction "RTS_10") (pintype "bidirectional"))
      (node (ref "U2") (pin "15") (pinfunction "1B1_15") (pintype "bidirectional"))
    )
    (net (code "70") (name "RTS_UC") (class "Default")
      (node (ref "U2") (pin "6") (pinfunction "1A1_6") (pintype "bidirectional"))
      (node (ref "U3") (pin "35") (pinfunction "PB14_35") (pintype "bidirectional"))
    )
    (net (code "71") (name "RX") (class "Default")
      (node (ref "JP1") (pin "4") (pinfunction "4_4") (pintype "passive"))
      (node (ref "U3") (pin "43") (pinfunction "PA10_43") (pintype "bidirectional"))
    )
    (net (code "72") (name "RXD_UB") (class "Default")
      (node (ref "U1") (pin "13") (pinfunction "RXD_13") (pintype "bidirectional"))
      (node (ref "U8") (pin "13") (pinfunction "2B1_13") (pintype "bidirectional"))
    )
    (net (code "73") (name "RXD_UC") (class "Default")
      (node (ref "U3") (pin "30") (pinfunction "PB11_30") (pintype "bidirectional"))
      (node (ref "U8") (pin "8") (pinfunction "2A1_8") (pintype "bidirectional"))
    )
    (net (code "74") (name "SIM_CLK") (class "Default")
      (node (ref "C12") (pin "1") (pinfunction "1_1") (pintype "passive"))
      (node (ref "J1") (pin "C3") (pinfunction "CLK_C3") (pintype "passive"))
      (node (ref "U1") (pin "38") (pinfunction "SIM_CLK_38") (pintype "bidirectional"))
    )
    (net (code "75") (name "SIM_DET") (class "Default")
      (node (ref "U1") (pin "42") (pinfunction "SIM_DET_42") (pintype "bidirectional"))
    )
    (net (code "76") (name "SIM_IO") (class "Default")
      (node (ref "C13") (pin "1") (pinfunction "1_1") (pintype "passive"))
      (node (ref "J1") (pin "C7") (pinfunction "I/O_C7") (pintype "passive"))
      (node (ref "U1") (pin "39") (pinfunction "SIM_IO_39") (pintype "bidirectional"))
    )
    (net (code "77") (name "SIM_RST") (class "Default")
      (node (ref "C10") (pin "1") (pinfunction "1_1") (pintype "passive"))
      (node (ref "J1") (pin "C2") (pinfunction "RST_C2") (pintype "passive"))
      (node (ref "U1") (pin "40") (pinfunction "SIM_RST_40") (pintype "bidirectional"))
    )
    (net (code "78") (name "SIM_VCC") (class "Default")
      (node (ref "C11") (pin "1") (pinfunction "1_1") (pintype "passive"))
      (node (ref "C14") (pin "1") (pinfunction "1_1") (pintype "passive"))
      (node (ref "J1") (pin "C1") (pinfunction "VCC_C1") (pintype "passive"))
      (node (ref "J1") (pin "C6") (pinfunction "VPP_C6") (pintype "passive"))
      (node (ref "U1") (pin "41") (pinfunction "VSIM_41") (pintype "bidirectional"))
    )
    (net (code "79") (name "STAT") (class "Default")
      (node (ref "R4") (pin "1") (pinfunction "1_1") (pintype "passive"))
      (node (ref "U$1") (pin "4") (pinfunction "STAT_4") (pintype "bidirectional"))
    )
    (net (code "80") (name "SW1") (class "Default")
      (node (ref "C7") (pin "2") (pinfunction "2_2") (pintype "passive"))
      (node (ref "U$1") (pin "19") (pinfunction "SW_19") (pintype "power_in"))
      (node (ref "U$1") (pin "20") (pinfunction "SW_20") (pintype "power_in"))
      (node (ref "U$4") (pin "P$1") (pinfunction "1_P$1") (pintype "passive"))
    )
    (net (code "81") (name "SW2") (class "Default")
      (node (ref "U$5") (pin "P$1") (pinfunction "P$1_P$1") (pintype "bidirectional"))
      (node (ref "U$6") (pin "P$1") (pinfunction "1_P$1") (pintype "passive"))
    )
    (net (code "82") (name "TX") (class "Default")
      (node (ref "JP1") (pin "3") (pinfunction "3_3") (pintype "passive"))
      (node (ref "U3") (pin "42") (pinfunction "PA9_42") (pintype "bidirectional"))
    )
    (net (code "83") (name "TXD_UB") (class "Default")
      (node (ref "U1") (pin "12") (pinfunction "TXD_12") (pintype "bidirectional"))
      (node (ref "U2") (pin "14") (pinfunction "1B2_14") (pintype "bidirectional"))
    )
    (net (code "84") (name "TXD_UC") (class "Default")
      (node (ref "U2") (pin "7") (pinfunction "1A2_7") (pintype "bidirectional"))
      (node (ref "U3") (pin "29") (pinfunction "PB10_29") (pintype "bidirectional"))
    )
    (net (code "85") (name "USB_DM") (class "Default")
      (node (ref "R6") (pin "2") (pinfunction "2_2") (pintype "passive"))
      (node (ref "R7") (pin "2") (pinfunction "2_2") (pintype "passive"))
      (node (ref "U$7") (pin "P$2") (pinfunction "P$2_P$2") (pintype "bidirectional"))
      (node (ref "X1") (pin "D-") (pinfunction "D-_D-") (pintype "bidirectional"))
    )
    (net (code "86") (name "USB_DM_UC") (class "Default")
      (node (ref "R6") (pin "1") (pinfunction "1_1") (pintype "passive"))
      (node (ref "U3") (pin "44") (pinfunction "PA11_44") (pintype "bidirectional"))
    )
    (net (code "87") (name "USB_DP") (class "Default")
      (node (ref "R5") (pin "2") (pinfunction "2_2") (pintype "passive"))
      (node (ref "U$1") (pin "2") (pinfunction "PSEL_2") (pintype "output"))
      (node (ref "U$7") (pin "P$1") (pinfunction "P$1_P$1") (pintype "bidirectional"))
      (node (ref "X1") (pin "D+") (pinfunction "D+_D+") (pintype "bidirectional"))
    )
    (net (code "88") (name "USB_DP_UC") (class "Default")
      (node (ref "R5") (pin "1") (pinfunction "1_1") (pintype "passive"))
      (node (ref "U3") (pin "45") (pinfunction "PA12_45") (pintype "bidirectional"))
    )
    (net (code "89") (name "VBAT") (class "Default")
      (node (ref "JP2") (pin "16") (pinfunction "16_16") (pintype "passive"))
      (node (ref "U3") (pin "1") (pinfunction "VBAT_1") (pintype "power_in"))
    )
    (net (code "90") (name "VBUS") (class "Default")
      (node (ref "JP3") (pin "1") (pinfunction "1_1") (pintype "passive"))
      (node (ref "U$3") (pin "ANODE") (pinfunction "ANODE_ANODE") (pintype "bidirectional"))
      (node (ref "X1") (pin "VBUS") (pinfunction "VBUS_VBUS") (pintype "bidirectional"))
    )
    (net (code "91") (name "VIN") (class "Default")
      (node (ref "C4") (pin "1") (pinfunction "1_1") (pintype "passive"))
      (node (ref "JP1") (pin "1") (pinfunction "1_1") (pintype "passive"))
      (node (ref "U$1") (pin "1") (pinfunction "VBUS_1") (pintype "power_in"))
      (node (ref "U$1") (pin "24") (pinfunction "VBUS_24") (pintype "passive"))
      (node (ref "U$3") (pin "CATHODE") (pinfunction "CATHODE_CATHODE") (pintype "bidirectional"))
    )
    (net (code "92") (name "V_BCKP") (class "Default")
      (node (ref "R1") (pin "2") (pinfunction "2_2") (pintype "passive"))
      (node (ref "U1") (pin "2") (pinfunction "V_BCKP_2") (pintype "bidirectional"))
    )
    (net (code "93") (name "V_INT") (class "Default")
      (node (ref "C21") (pin "1") (pinfunction "1_1") (pintype "passive"))
      (node (ref "C22") (pin "1") (pinfunction "1_1") (pintype "passive"))
      (node (ref "U1") (pin "4") (pinfunction "V_INT_4") (pintype "bidirectional"))
      (node (ref "U2") (pin "2") (pinfunction "VCCB_2") (pintype "bidirectional"))
      (node (ref "U8") (pin "2") (pinfunction "VCCB_2") (pintype "bidirectional"))
    )
    (net (code "94") (name "WKP") (class "Default")
      (node (ref "JP1") (pin "5") (pinfunction "5_5") (pintype "passive"))
      (node (ref "U3") (pin "14") (pinfunction "WKUP/PA0_14") (pintype "bidirectional"))
    )
    (net (code "95") (name "unconnected-(MODE-Pad4)") (class "Default")
      (node (ref "MODE") (pin "4") (pinfunction "4_4") (pintype "passive"))
    )
    (net (code "96") (name "unconnected-(RESET-Pad1)") (class "Default")
      (node (ref "RESET") (pin "1") (pinfunction "1_1") (pintype "passive"))
    )
    (net (code "97") (name "unconnected-(U1-DCD-Pad8)") (class "Default")
      (node (ref "U1") (pin "8") (pinfunction "DCD_8") (pintype "bidirectional"))
    )
    (net (code "98") (name "unconnected-(U1-DSR-Pad6)") (class "Default")
      (node (ref "U1") (pin "6") (pinfunction "DSR_6") (pintype "bidirectional"))
    )
    (net (code "99") (name "unconnected-(U1-GPIO1-Pad16)") (class "Default")
      (node (ref "U1") (pin "16") (pinfunction "GPIO1_16") (pintype "bidirectional"))
    )
    (net (code "100") (name "unconnected-(U1-GPIO2-Pad23)") (class "Default")
      (node (ref "U1") (pin "23") (pinfunction "GPIO2_23") (pintype "bidirectional"))
    )
    (net (code "101") (name "unconnected-(U1-GPIO3-Pad24)") (class "Default")
      (node (ref "U1") (pin "24") (pinfunction "GPIO3_24") (pintype "bidirectional"))
    )
    (net (code "102") (name "unconnected-(U1-GPIO4-Pad25)") (class "Default")
      (node (ref "U1") (pin "25") (pinfunction "GPIO4_25") (pintype "bidirectional"))
    )
    (net (code "103") (name "unconnected-(U1-I2S_CLK-Pad36)") (class "Default")
      (node (ref "U1") (pin "36") (pinfunction "I2S_CLK_36") (pintype "bidirectional"))
    )
    (net (code "104") (name "unconnected-(U1-I2S_RXD-Pad37)") (class "Default")
      (node (ref "U1") (pin "37") (pinfunction "I2S_RXD_37") (pintype "bidirectional"))
    )
    (net (code "105") (name "unconnected-(U1-I2S_TXD-Pad35)") (class "Default")
      (node (ref "U1") (pin "35") (pinfunction "I2S_TXD_35") (pintype "bidirectional"))
    )
    (net (code "106") (name "unconnected-(U1-I2S_WA-Pad34)") (class "Default")
      (node (ref "U1") (pin "34") (pinfunction "I2S_WA_34") (pintype "bidirectional"))
    )
    (net (code "107") (name "unconnected-(U1-MIC_BIAS-Pad46)") (class "Default")
      (node (ref "U1") (pin "46") (pinfunction "MIC_BIAS_46") (pintype "bidirectional"))
    )
    (net (code "108") (name "unconnected-(U1-MIC_GND-Pad47)") (class "Default")
      (node (ref "U1") (pin "47") (pinfunction "MIC_GND_47") (pintype "bidirectional"))
    )
    (net (code "109") (name "unconnected-(U1-MIC_N-Pad48)") (class "Default")
      (node (ref "U1") (pin "48") (pinfunction "MIC_N_48") (pintype "bidirectional"))
    )
    (net (code "110") (name "unconnected-(U1-MIC_P-Pad49)") (class "Default")
      (node (ref "U1") (pin "49") (pinfunction "MIC_P_49") (pintype "bidirectional"))
    )
    (net (code "111") (name "unconnected-(U1-RSVD-Pad19)") (class "Default")
      (node (ref "U1") (pin "19") (pinfunction "RSVD_19") (pintype "bidirectional"))
    )
    (net (code "112") (name "unconnected-(U1-RSVD-Pad31)") (class "Default")
      (node (ref "U1") (pin "31") (pinfunction "RSVD_31") (pintype "bidirectional"))
    )
    (net (code "113") (name "unconnected-(U1-RXD_AUX{slash}USB_D--Pad28)") (class "Default")
      (node (ref "U1") (pin "28") (pinfunction "RXD_AUX/USB_D-_28") (pintype "bidirectional"))
    )
    (net (code "114") (name "unconnected-(U1-SCL-Pad27)") (class "Default")
      (node (ref "U1") (pin "27") (pinfunction "SCL_27") (pintype "bidirectional"))
    )
    (net (code "115") (name "unconnected-(U1-SDA-Pad26)") (class "Default")
      (node (ref "U1") (pin "26") (pinfunction "SDA_26") (pintype "bidirectional"))
    )
    (net (code "116") (name "unconnected-(U1-SPK_N-Pad45)") (class "Default")
      (node (ref "U1") (pin "45") (pinfunction "SPK_N_45") (pintype "bidirectional"))
    )
    (net (code "117") (name "unconnected-(U1-SPK_P-Pad44)") (class "Default")
      (node (ref "U1") (pin "44") (pinfunction "SPK_P_44") (pintype "bidirectional"))
    )
    (net (code "118") (name "unconnected-(U1-TXD_AUX{slash}USB_D+-Pad29)") (class "Default")
      (node (ref "U1") (pin "29") (pinfunction "TXD_AUX/USB_D+_29") (pintype "bidirectional"))
    )
    (net (code "119") (name "unconnected-(U1-VUSB_DET-Pad17)") (class "Default")
      (node (ref "U1") (pin "17") (pinfunction "VUSB_DET_17") (pintype "bidirectional"))
    )
    (net (code "120") (name "unconnected-(U2-2A1-Pad8)") (class "Default")
      (node (ref "U2") (pin "8") (pinfunction "2A1_8") (pintype "bidirectional"))
    )
    (net (code "121") (name "unconnected-(U2-2A2-Pad9)") (class "Default")
      (node (ref "U2") (pin "9") (pinfunction "2A2_9") (pintype "bidirectional"))
    )
    (net (code "122") (name "unconnected-(U2-2B1-Pad13)") (class "Default")
      (node (ref "U2") (pin "13") (pinfunction "2B1_13") (pintype "bidirectional"))
    )
    (net (code "123") (name "unconnected-(U2-2B2-Pad12)") (class "Default")
      (node (ref "U2") (pin "12") (pinfunction "2B2_12") (pintype "bidirectional"))
    )
    (net (code "124") (name "unconnected-(U8-2A2-Pad9)") (class "Default")
      (node (ref "U8") (pin "9") (pinfunction "2A2_9") (pintype "bidirectional"))
    )
    (net (code "125") (name "unconnected-(U8-2B2-Pad12)") (class "Default")
      (node (ref "U8") (pin "12") (pinfunction "2B2_12") (pintype "bidirectional"))
    )
    (net (code "126") (name "~{CE}") (class "Default")
      (node (ref "R17") (pin "1") (pinfunction "1_1") (pintype "passive"))
      (node (ref "U$1") (pin "9") (pinfunction "~{CE}_9") (pintype "output"))
    )
    (net (code "127") (name "~{LOW_BAT_INT_UC}") (class "Default")
      (node (ref "R21") (pin "1") (pinfunction "1_1") (pintype "passive"))
      (node (ref "U3") (pin "2") (pinfunction "PC13_2") (pintype "bidirectional"))
      (node (ref "U4") (pin "5") (pinfunction "ALT_5") (pintype "bidirectional"))
    )
    (net (code "128") (name "~{LVLOE_UC}") (class "Default")
      (node (ref "R3") (pin "1") (pinfunction "1_1") (pintype "passive"))
      (node (ref "U2") (pin "1") (pinfunction "1/OE_1") (pintype "bidirectional"))
      (node (ref "U2") (pin "16") (pinfunction "2/OE_16") (pintype "bidirectional"))
      (node (ref "U3") (pin "36") (pinfunction "PB15_36") (pintype "bidirectional"))
      (node (ref "U8") (pin "1") (pinfunction "1/OE_1") (pintype "bidirectional"))
      (node (ref "U8") (pin "16") (pinfunction "2/OE_16") (pintype "bidirectional"))
    )
    (net (code "129") (name "~{MODE}") (class "Default")
      (node (ref "MODE") (pin "3") (pinfunction "3_3") (pintype "passive"))
      (node (ref "U3") (pin "38") (pinfunction "PC7_38") (pintype "bidirectional"))
    )
    (net (code "130") (name "~{RST}") (class "Default")
      (node (ref "C6") (pin "1") (pinfunction "1_1") (pintype "passive"))
      (node (ref "JP2") (pin "17") (pinfunction "17_17") (pintype "passive"))
      (node (ref "R8") (pin "1") (pinfunction "1_1") (pintype "passive"))
      (node (ref "RESET") (pin "2") (pinfunction "2_2") (pintype "passive"))
      (node (ref "U3") (pin "7") (pinfunction "NRST_7") (pintype "power_in"))
    )
  )
)
